# EN-C200_RA0_PWR.net
KiCad netlist of a schematic drawn in Altium Designer
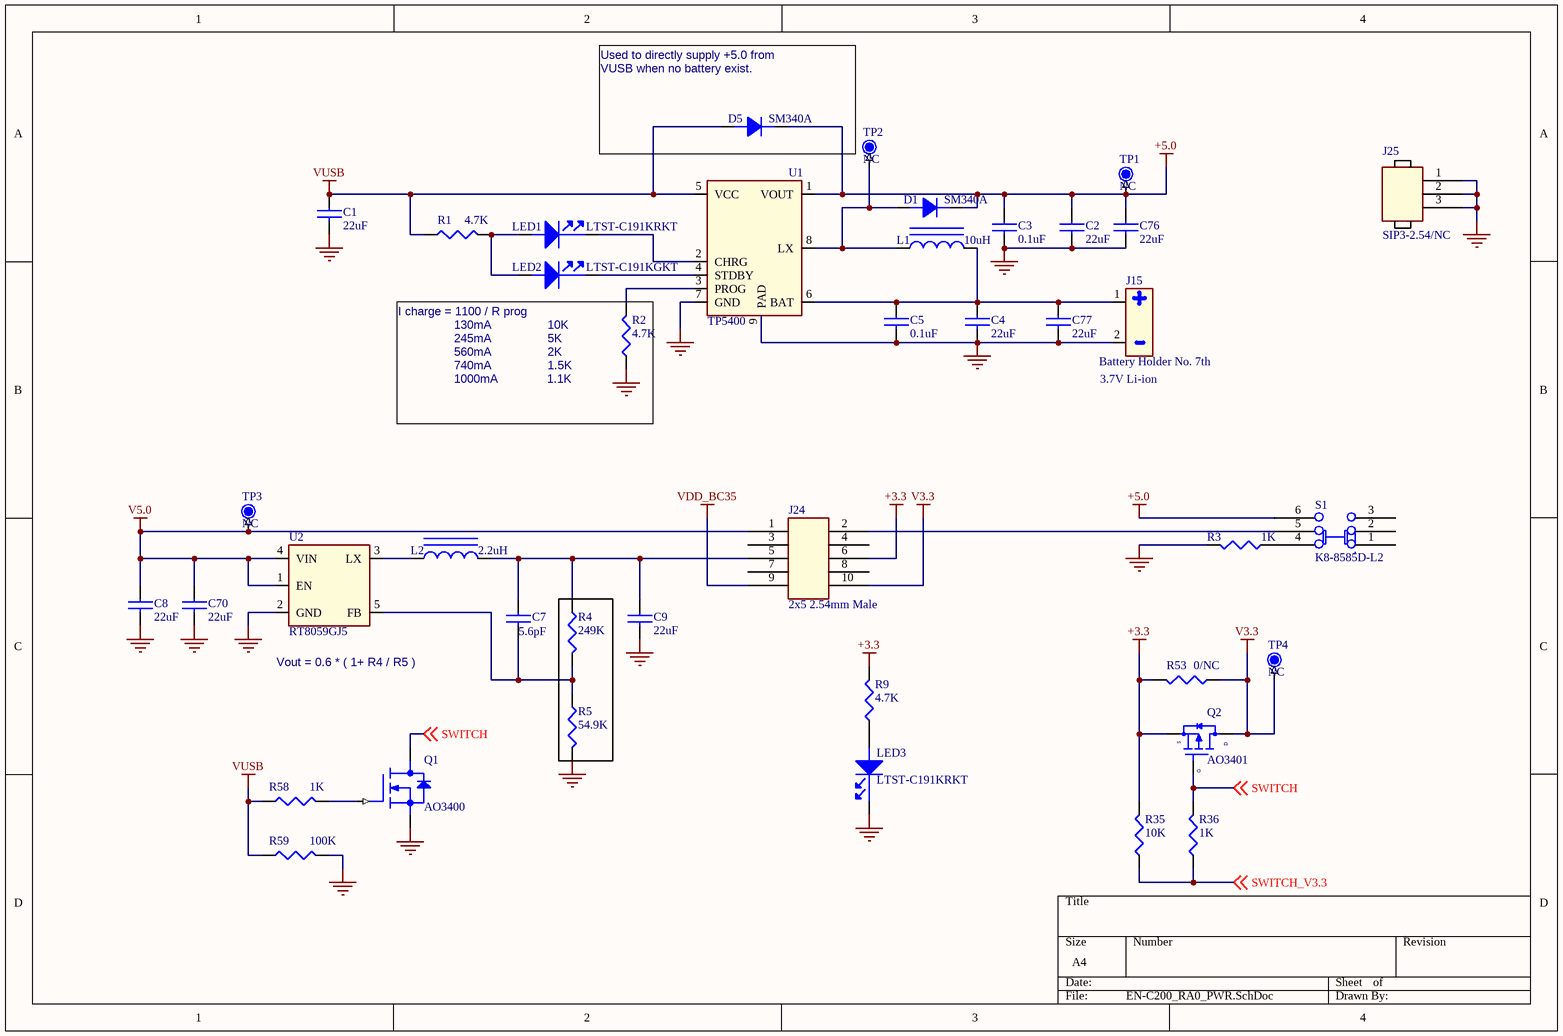
[diagram p0: EN-C200_RA0_PWR.SchDoc]

(export (version "E")
  (design (tool "Eeschema 10.0.6"))
  (components
    (comp (ref "C1") (value "22uF") (footprint "SC0805") (libsource (lib "EN-C200_RA0") (part "CAP NP")))
    (comp (ref "C2") (value "22uF") (footprint "SC0805") (libsource (lib "EN-C200_RA0") (part "CAP NP")))
    (comp (ref "C3") (value "0.1uF") (footprint "SC0603") (libsource (lib "EN-C200_RA0") (part "CAP NP")))
    (comp (ref "C4") (value "22uF") (footprint "SC0805") (libsource (lib "EN-C200_RA0") (part "CAP NP")))
    (comp (ref "C5") (value "0.1uF") (footprint "SC0603") (libsource (lib "EN-C200_RA0") (part "CAP NP")))
    (comp (ref "C7") (value "5.6pF") (footprint "SC0603") (libsource (lib "EN-C200_RA0") (part "CAP NP")))
    (comp (ref "C8") (value "22uF") (footprint "SC0805") (libsource (lib "EN-C200_RA0") (part "CAP NP")))
    (comp (ref "C9") (value "22uF") (footprint "SC0805") (libsource (lib "EN-C200_RA0") (part "CAP NP")))
    (comp (ref "C70") (value "22uF") (footprint "SC0805") (libsource (lib "EN-C200_RA0") (part "CAP NP")))
    (comp (ref "C76") (value "22uF") (footprint "SC0805") (libsource (lib "EN-C200_RA0") (part "CAP NP")))
    (comp (ref "C77") (value "22uF") (footprint "SC0805") (libsource (lib "EN-C200_RA0") (part "CAP NP")))
    (comp (ref "D1") (value "SM340A") (footprint "SD1714") (libsource (lib "EN-C200_RA0") (part "DIODE")))
    (comp (ref "D5") (value "SM340A") (footprint "SD1714") (libsource (lib "EN-C200_RA0") (part "DIODE")))
    (comp (ref "J15")
      (value "Battery Holder No. 7th")
      (footprint "BX0034")
      (libsource (lib "EN-C200_RA0") (part "BX0034"))
    )
    (comp (ref "J24")
      (value "2x5 2.54mm Male")
      (footprint "SIP-2X5P-100")
      (libsource (lib "EN-C200_RA0") (part "CON10A"))
    )
    (comp (ref "J25")
      (value "SIP3-2.54/NC")
      (footprint "SIP-3P")
      (libsource (lib "EN-C200_RA0") (part "HEADER3"))
    )
    (comp (ref "L1")
      (value "10uH")
      (footprint "SPL0505B")
      (libsource (lib "EN-C200_RA0") (part "TOROID IRON"))
    )
    (comp (ref "L2")
      (value "2.2uH")
      (footprint "SL1008")
      (libsource (lib "EN-C200_RA0") (part "TOROID IRON"))
    )
    (comp (ref "LED1")
      (value "LTST-C191KRKT")
      (footprint "HSD0603-LED")
      (libsource (lib "EN-C200_RA0") (part "LED"))
    )
    (comp (ref "LED2")
      (value "LTST-C191KGKT")
      (footprint "HSD0603-LED")
      (libsource (lib "EN-C200_RA0") (part "LED"))
    )
    (comp (ref "LED3")
      (value "LTST-C191KRKT")
      (footprint "HSD0603-LED")
      (libsource (lib "EN-C200_RA0") (part "LED"))
    )
    (comp (ref "Q1") (value "AO3400") (footprint "SOT23") (libsource (lib "EN-C200_RA0") (part "MPF6661")))
    (comp (ref "Q2") (value "AO3401") (footprint "SOT23") (libsource (lib "EN-C200_RA0") (part "A03401")))
    (comp (ref "R1") (value "4.7K") (footprint "SR0603") (libsource (lib "EN-C200_RA0") (part "RESISTOR")))
    (comp (ref "R2") (value "4.7K") (footprint "SR0603") (libsource (lib "EN-C200_RA0") (part "RESISTOR")))
    (comp (ref "R3") (value "1K") (footprint "SR0603") (libsource (lib "EN-C200_RA0") (part "RESISTOR")))
    (comp (ref "R4") (value "249K") (footprint "SR0603") (libsource (lib "EN-C200_RA0") (part "RESISTOR")))
    (comp (ref "R5") (value "54.9K") (footprint "SR0603") (libsource (lib "EN-C200_RA0") (part "RESISTOR")))
    (comp (ref "R9") (value "4.7K") (footprint "SR0603") (libsource (lib "EN-C200_RA0") (part "RESISTOR")))
    (comp (ref "R35") (value "10K") (footprint "SR0603") (libsource (lib "EN-C200_RA0") (part "RESISTOR")))
    (comp (ref "R36") (value "1K") (footprint "SR0603") (libsource (lib "EN-C200_RA0") (part "RESISTOR")))
    (comp (ref "R53") (value "0/NC") (footprint "SR0603") (libsource (lib "EN-C200_RA0") (part "RESISTOR")))
    (comp (ref "R58") (value "1K") (footprint "SR0603") (libsource (lib "EN-C200_RA0") (part "RESISTOR")))
    (comp (ref "R59") (value "100K") (footprint "SR0603") (libsource (lib "EN-C200_RA0") (part "RESISTOR")))
    (comp (ref "S1")
      (value "K8-8585D-L2")
      (footprint "SW2X3-100")
      (libsource (lib "EN-C200_RA0") (part "SW_PUSH6"))
    )
    (comp (ref "TP1") (value "NC") (footprint "TP32-SMD") (libsource (lib "EN-C200_RA0") (part "TP")))
    (comp (ref "TP2") (value "NC") (footprint "TP32-SMD") (libsource (lib "EN-C200_RA0") (part "TP")))
    (comp (ref "TP3") (value "NC") (footprint "TP32-SMD") (libsource (lib "EN-C200_RA0") (part "TP")))
    (comp (ref "TP4") (value "NC") (footprint "TP32-SMD") (libsource (lib "EN-C200_RA0") (part "TP")))
    (comp (ref "U1")
      (value "TP5400")
      (footprint "SOP8-50-150B")
      (libsource (lib "EN-C200_RA0") (part "TP5400"))
    )
    (comp (ref "U2")
      (value "RT8059GJ5")
      (footprint "SOT23-5")
      (libsource (lib "EN-C200_RA0") (part "RT8059"))
    )
  )
  (nets
    (net (code "1") (name "+3.3") (class "Default")
      (node (ref "J24") (pin "6") (pinfunction "6_6") (pintype "passive"))
      (node (ref "Q2") (pin "2") (pinfunction "S_2") (pintype "passive"))
      (node (ref "R35") (pin "2") (pinfunction "2_2") (pintype "passive"))
      (node (ref "R53") (pin "2") (pinfunction "2_2") (pintype "passive"))
      (node (ref "R9") (pin "2") (pinfunction "2_2") (pintype "passive"))
    )
    (net (code "2") (name "+5.0") (class "Default")
      (node (ref "C2") (pin "1") (pinfunction "1_1") (pintype "passive"))
      (node (ref "C3") (pin "1") (pinfunction "1_1") (pintype "passive"))
      (node (ref "C76") (pin "1") (pinfunction "1_1") (pintype "passive"))
      (node (ref "D1") (pin "2") (pinfunction "K_2") (pintype "passive"))
      (node (ref "D5") (pin "2") (pinfunction "K_2") (pintype "passive"))
      (node (ref "S1") (pin "6") (pinfunction "6_6") (pintype "passive"))
      (node (ref "TP1") (pin "1") (pinfunction "1_1") (pintype "input"))
      (node (ref "U1") (pin "1") (pinfunction "VOUT_1") (pintype "power_in"))
    )
    (net (code "3") (name "GND") (class "Default")
      (node (ref "C1") (pin "2") (pinfunction "2_2") (pintype "passive"))
      (node (ref "C2") (pin "2") (pinfunction "2_2") (pintype "passive"))
      (node (ref "C3") (pin "2") (pinfunction "2_2") (pintype "passive"))
      (node (ref "C4") (pin "2") (pinfunction "2_2") (pintype "passive"))
      (node (ref "C5") (pin "2") (pinfunction "2_2") (pintype "passive"))
      (node (ref "C70") (pin "2") (pinfunction "2_2") (pintype "passive"))
      (node (ref "C76") (pin "2") (pinfunction "2_2") (pintype "passive"))
      (node (ref "C77") (pin "2") (pinfunction "2_2") (pintype "passive"))
      (node (ref "C8") (pin "2") (pinfunction "2_2") (pintype "passive"))
      (node (ref "C9") (pin "2") (pinfunction "2_2") (pintype "passive"))
      (node (ref "J15") (pin "2") (pinfunction "2_2") (pintype "passive"))
      (node (ref "J25") (pin "1") (pinfunction "1_1") (pintype "passive"))
      (node (ref "J25") (pin "2") (pinfunction "2_2") (pintype "passive"))
      (node (ref "J25") (pin "3") (pinfunction "3_3") (pintype "passive"))
      (node (ref "LED3") (pin "2") (pinfunction "2_2") (pintype "passive"))
      (node (ref "Q1") (pin "2") (pinfunction "S_2") (pintype "passive"))
      (node (ref "R2") (pin "1") (pinfunction "1_1") (pintype "passive"))
      (node (ref "R3") (pin "2") (pinfunction "2_2") (pintype "passive"))
      (node (ref "R5") (pin "2") (pinfunction "2_2") (pintype "passive"))
      (node (ref "R59") (pin "2") (pinfunction "2_2") (pintype "passive"))
      (node (ref "U1") (pin "7") (pinfunction "GND_7") (pintype "power_in"))
      (node (ref "U1") (pin "9") (pinfunction "PAD_9") (pintype "passive"))
      (node (ref "U2") (pin "2") (pinfunction "GND_2") (pintype "power_in"))
    )
    (net (code "4") (name "Net-(C7-Pad1)") (class "Default")
      (node (ref "C7") (pin "1") (pinfunction "1_1") (pintype "passive"))
      (node (ref "C9") (pin "1") (pinfunction "1_1") (pintype "passive"))
      (node (ref "J24") (pin "5") (pinfunction "5_5") (pintype "passive"))
      (node (ref "L2") (pin "2") (pinfunction "2_2") (pintype "passive"))
      (node (ref "R4") (pin "1") (pinfunction "1_1") (pintype "passive"))
    )
    (net (code "5") (name "Net-(D1-A)") (class "Default")
      (node (ref "D1") (pin "1") (pinfunction "A_1") (pintype "passive"))
      (node (ref "L1") (pin "1") (pinfunction "1_1") (pintype "passive"))
      (node (ref "TP2") (pin "1") (pinfunction "1_1") (pintype "input"))
      (node (ref "U1") (pin "8") (pinfunction "LX_8") (pintype "passive"))
    )
    (net (code "6") (name "Net-(J24-Pad2)") (class "Default")
      (node (ref "J24") (pin "2") (pinfunction "2_2") (pintype "passive"))
      (node (ref "S1") (pin "5") (pinfunction "5_5") (pintype "passive"))
    )
    (net (code "7") (name "Net-(LED1-Pad1)") (class "Default")
      (node (ref "LED1") (pin "1") (pinfunction "1_1") (pintype "passive"))
      (node (ref "LED2") (pin "1") (pinfunction "1_1") (pintype "passive"))
      (node (ref "R1") (pin "2") (pinfunction "2_2") (pintype "passive"))
    )
    (net (code "8") (name "Net-(LED3-Pad1)") (class "Default")
      (node (ref "LED3") (pin "1") (pinfunction "1_1") (pintype "passive"))
      (node (ref "R9") (pin "1") (pinfunction "1_1") (pintype "passive"))
    )
    (net (code "9") (name "Net-(Q1-G)") (class "Default")
      (node (ref "Q1") (pin "1") (pinfunction "G_1") (pintype "input"))
      (node (ref "R58") (pin "2") (pinfunction "2_2") (pintype "passive"))
    )
    (net (code "10") (name "Net-(R3-Pad1)") (class "Default")
      (node (ref "R3") (pin "1") (pinfunction "1_1") (pintype "passive"))
      (node (ref "S1") (pin "4") (pinfunction "4_4") (pintype "passive"))
    )
    (net (code "11") (name "Net-(U1-BAT)") (class "Default")
      (node (ref "C4") (pin "1") (pinfunction "1_1") (pintype "passive"))
      (node (ref "C5") (pin "1") (pinfunction "1_1") (pintype "passive"))
      (node (ref "C77") (pin "1") (pinfunction "1_1") (pintype "passive"))
      (node (ref "J15") (pin "1") (pinfunction "1_1") (pintype "passive"))
      (node (ref "L1") (pin "2") (pinfunction "2_2") (pintype "passive"))
      (node (ref "U1") (pin "6") (pinfunction "BAT_6") (pintype "power_in"))
    )
    (net (code "12") (name "Net-(U1-CHRG)") (class "Default")
      (node (ref "LED1") (pin "2") (pinfunction "2_2") (pintype "passive"))
      (node (ref "U1") (pin "2") (pinfunction "CHRG_2") (pintype "passive"))
    )
    (net (code "13") (name "Net-(U1-PROG)") (class "Default")
      (node (ref "R2") (pin "2") (pinfunction "2_2") (pintype "passive"))
      (node (ref "U1") (pin "3") (pinfunction "PROG_3") (pintype "passive"))
    )
    (net (code "14") (name "Net-(U1-STDBY)") (class "Default")
      (node (ref "LED2") (pin "2") (pinfunction "2_2") (pintype "passive"))
      (node (ref "U1") (pin "4") (pinfunction "STDBY_4") (pintype "passive"))
    )
    (net (code "15") (name "Net-(U2-FB)") (class "Default")
      (node (ref "C7") (pin "2") (pinfunction "2_2") (pintype "passive"))
      (node (ref "R4") (pin "2") (pinfunction "2_2") (pintype "passive"))
      (node (ref "R5") (pin "1") (pinfunction "1_1") (pintype "passive"))
      (node (ref "U2") (pin "5") (pinfunction "FB_5") (pintype "passive"))
    )
    (net (code "16") (name "Net-(U2-LX)") (class "Default")
      (node (ref "L2") (pin "1") (pinfunction "1_1") (pintype "passive"))
      (node (ref "U2") (pin "3") (pinfunction "LX_3") (pintype "passive"))
    )
    (net (code "17") (name "SWITCH") (class "Default")
      (node (ref "Q1") (pin "3") (pinfunction "D_3") (pintype "passive"))
      (node (ref "Q2") (pin "1") (pinfunction "G_1") (pintype "passive"))
      (node (ref "R36") (pin "2") (pinfunction "2_2") (pintype "passive"))
    )
    (net (code "18") (name "SWITCH_V3.3") (class "Default")
      (node (ref "R35") (pin "1") (pinfunction "1_1") (pintype "passive"))
      (node (ref "R36") (pin "1") (pinfunction "1_1") (pintype "passive"))
    )
    (net (code "19") (name "V3.3") (class "Default")
      (node (ref "J24") (pin "10") (pinfunction "10_10") (pintype "passive"))
      (node (ref "Q2") (pin "3") (pinfunction "D_3") (pintype "passive"))
      (node (ref "R53") (pin "1") (pinfunction "1_1") (pintype "passive"))
      (node (ref "TP4") (pin "1") (pinfunction "1_1") (pintype "input"))
    )
    (net (code "20") (name "V5.0") (class "Default")
      (node (ref "C70") (pin "1") (pinfunction "1_1") (pintype "passive"))
      (node (ref "C8") (pin "1") (pinfunction "1_1") (pintype "passive"))
      (node (ref "J24") (pin "1") (pinfunction "1_1") (pintype "passive"))
      (node (ref "TP3") (pin "1") (pinfunction "1_1") (pintype "input"))
      (node (ref "U2") (pin "1") (pinfunction "EN_1") (pintype "passive"))
      (node (ref "U2") (pin "4") (pinfunction "VIN_4") (pintype "power_in"))
    )
    (net (code "21") (name "VDD_BC35") (class "Default")
      (node (ref "J24") (pin "9") (pinfunction "9_9") (pintype "passive"))
    )
    (net (code "22") (name "VUSB") (class "Default")
      (node (ref "C1") (pin "1") (pinfunction "1_1") (pintype "passive"))
      (node (ref "D5") (pin "1") (pinfunction "A_1") (pintype "passive"))
      (node (ref "R1") (pin "1") (pinfunction "1_1") (pintype "passive"))
      (node (ref "R58") (pin "1") (pinfunction "1_1") (pintype "passive"))
      (node (ref "R59") (pin "1") (pinfunction "1_1") (pintype "passive"))
      (node (ref "U1") (pin "5") (pinfunction "VCC_5") (pintype "power_in"))
    )
    (net (code "23") (name "unconnected-(J24-Pad3)") (class "Default")
      (node (ref "J24") (pin "3") (pinfunction "3_3") (pintype "passive"))
    )
    (net (code "24") (name "unconnected-(J24-Pad4)") (class "Default")
      (node (ref "J24") (pin "4") (pinfunction "4_4") (pintype "passive"))
    )
    (net (code "25") (name "unconnected-(J24-Pad7)") (class "Default")
      (node (ref "J24") (pin "7") (pinfunction "7_7") (pintype "passive"))
    )
    (net (code "26") (name "unconnected-(J24-Pad8)") (class "Default")
      (node (ref "J24") (pin "8") (pinfunction "8_8") (pintype "passive"))
    )
    (net (code "27") (name "unconnected-(S1-Pad1)") (class "Default")
      (node (ref "S1") (pin "1") (pinfunction "1_1") (pintype "passive"))
    )
    (net (code "28") (name "unconnected-(S1-Pad2)") (class "Default")
      (node (ref "S1") (pin "2") (pinfunction "2_2") (pintype "passive"))
    )
    (net (code "29") (name "unconnected-(S1-Pad3)") (class "Default")
      (node (ref "S1") (pin "3") (pinfunction "3_3") (pintype "passive"))
    )
  )
)
